# PCB_Actualizada_AMR.net
KiCad netlist of a schematic drawn in EasyEDA
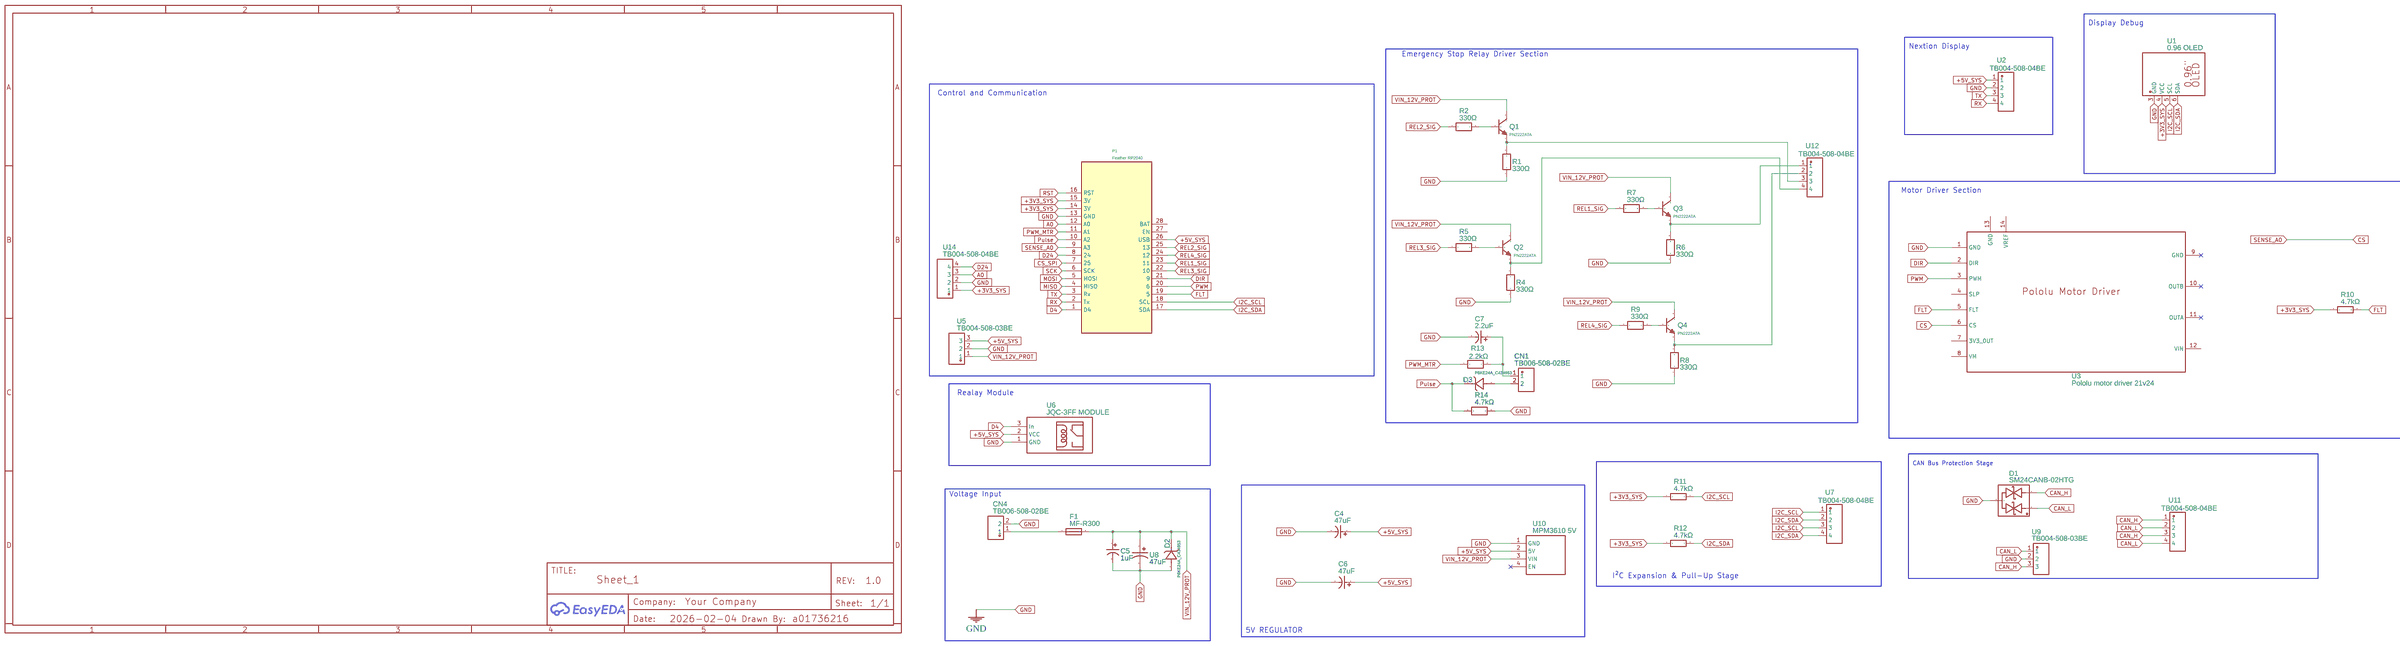
[diagram p0: schematic sheet]

(export (version "E")
  (design (tool "Eeschema 10.0.6"))
  (components
    (comp (ref "C4")
      (value "47uF")
      (fields
        (field (name "Manufacturer Part") "KM476M016D11RR0VH2FP0")
        (field (name "Manufacturer") "Chengx(承兴)")
      )
      (libsource (lib "") (part "47uF 16V Aluminum electrolytic capacitors"))
    )
    (comp (ref "C5")
      (value "1uF")
      (fields
        (field (name "Manufacturer Part") "KM105M250E11RR0VH2FP0")
        (field (name "Manufacturer") "Chengx(承兴)")
      )
      (libsource (lib "") (part "1uF 250V 6.3*11"))
    )
    (comp (ref "C6")
      (value "47uF")
      (fields
        (field (name "Manufacturer Part") "KM476M016D11RR0VH2FP0")
        (field (name "Manufacturer") "Chengx(承兴)")
      )
      (libsource (lib "") (part "47uF 16V Aluminum electrolytic capacitors"))
    )
    (comp (ref "C7")
      (value "2.2uF")
      (fields
        (field (name "Manufacturer Part") "KM476M016D11RR0VH2FP0")
        (field (name "Manufacturer") "Chengx(承兴)")
      )
      (libsource (lib "") (part "47uF 16V Aluminum electrolytic capacitors"))
    )
    (comp (ref "CN1") (value "TB006-508-02BE") (libsource (lib "") (part "TB006-508-02BE")))
    (comp (ref "CN4") (value "TB006-508-02BE") (libsource (lib "") (part "TB006-508-02BE_1")))
    (comp (ref "D1")
      (value "SM24CANB-02HTG")
      (fields (field (name "Manufacturer") "Littelfuse(美国力特)"))
      (libsource (lib "") (part "SM24CANB-02HTG"))
    )
    (comp (ref "D2")
      (value "P6KE24A_C434953")
      (fields (field (name "Manufacturer Part") "P6KE24A") (field (name "Manufacturer") "CREATEK(达晶微)"))
      (libsource (lib "") (part "P6KE24A_C434953"))
    )
    (comp (ref "D3")
      (value "P6KE24A_C434953")
      (fields (field (name "Manufacturer Part") "P6KE24A") (field (name "Manufacturer") "CREATEK(达晶微)"))
      (libsource (lib "") (part "P6KE24A_C434953_1"))
    )
    (comp (ref "F1")
      (value "MF-R300")
      (fields (field (name "Manufacturer") "BOURNS"))
      (libsource (lib "") (part "MF-R300"))
    )
    (comp (ref "P1")
      (value "Feather RP2040")
      (fields (field (name "Manufacturer") "Adafruit"))
      (libsource (lib "") (part "Feather RP2040"))
    )
    (comp (ref "Q1")
      (value "PN2222ATA")
      (fields (field (name "Manufacturer") "onsemi(安森美)"))
      (libsource (lib "") (part "PN2222ATA"))
    )
    (comp (ref "Q2")
      (value "PN2222ATA")
      (fields (field (name "Manufacturer") "onsemi(安森美)"))
      (libsource (lib "") (part "PN2222ATA"))
    )
    (comp (ref "Q3")
      (value "PN2222ATA")
      (fields (field (name "Manufacturer") "onsemi(安森美)"))
      (libsource (lib "") (part "PN2222ATA"))
    )
    (comp (ref "Q4")
      (value "PN2222ATA")
      (fields (field (name "Manufacturer") "onsemi(安森美)"))
      (libsource (lib "") (part "PN2222ATA"))
    )
    (comp (ref "R1")
      (value "330Ω")
      (fields
        (field (name "Manufacturer Part") "RN 1/4W 330R F T/B A1")
        (field (name "Manufacturer") "Tyohm(幸亚电阻)")
      )
      (libsource (lib "") (part "RN 1/4W 330R F T/B A1"))
    )
    (comp (ref "R2")
      (value "330Ω")
      (fields
        (field (name "Manufacturer Part") "RN 1/4W 330R F T/B A1")
        (field (name "Manufacturer") "Tyohm(幸亚电阻)")
      )
      (libsource (lib "") (part "RN 1/4W 330R F T/B A1_1"))
    )
    (comp (ref "R4")
      (value "330Ω")
      (fields
        (field (name "Manufacturer Part") "RN 1/4W 330R F T/B A1")
        (field (name "Manufacturer") "Tyohm(幸亚电阻)")
      )
      (libsource (lib "") (part "RN 1/4W 330R F T/B A1"))
    )
    (comp (ref "R5")
      (value "330Ω")
      (fields
        (field (name "Manufacturer Part") "RN 1/4W 330R F T/B A1")
        (field (name "Manufacturer") "Tyohm(幸亚电阻)")
      )
      (libsource (lib "") (part "RN 1/4W 330R F T/B A1_1"))
    )
    (comp (ref "R6")
      (value "330Ω")
      (fields
        (field (name "Manufacturer Part") "RN 1/4W 330R F T/B A1")
        (field (name "Manufacturer") "Tyohm(幸亚电阻)")
      )
      (libsource (lib "") (part "RN 1/4W 330R F T/B A1"))
    )
    (comp (ref "R7")
      (value "330Ω")
      (fields
        (field (name "Manufacturer Part") "RN 1/4W 330R F T/B A1")
        (field (name "Manufacturer") "Tyohm(幸亚电阻)")
      )
      (libsource (lib "") (part "RN 1/4W 330R F T/B A1_1"))
    )
    (comp (ref "R8")
      (value "330Ω")
      (fields
        (field (name "Manufacturer Part") "RN 1/4W 330R F T/B A1")
        (field (name "Manufacturer") "Tyohm(幸亚电阻)")
      )
      (libsource (lib "") (part "RN 1/4W 330R F T/B A1"))
    )
    (comp (ref "R9")
      (value "330Ω")
      (fields
        (field (name "Manufacturer Part") "RN 1/4W 330R F T/B A1")
        (field (name "Manufacturer") "Tyohm(幸亚电阻)")
      )
      (libsource (lib "") (part "RN 1/4W 330R F T/B A1_1"))
    )
    (comp (ref "R10")
      (value "4.7kΩ")
      (fields
        (field (name "Manufacturer Part") "CF1/4W-4.7KΩ±5% T")
        (field (name "Manufacturer") "CCO(千志电子)")
      )
      (libsource (lib "") (part "CF1/4W-4.7KΩ±5% T52"))
    )
    (comp (ref "R11")
      (value "4.7kΩ")
      (fields
        (field (name "Manufacturer Part") "CF1/4W-4.7KΩ±5% T")
        (field (name "Manufacturer") "CCO(千志电子)")
      )
      (libsource (lib "") (part "CF1/4W-4.7KΩ±5% T52"))
    )
    (comp (ref "R12")
      (value "4.7kΩ")
      (fields
        (field (name "Manufacturer Part") "CF1/4W-4.7KΩ±5% T")
        (field (name "Manufacturer") "CCO(千志电子)")
      )
      (libsource (lib "") (part "CF1/4W-4.7KΩ±5% T52"))
    )
    (comp (ref "R13")
      (value "2.2kΩ")
      (fields
        (field (name "Manufacturer Part") "RN 1/4W 330R F T/B A1")
        (field (name "Manufacturer") "Tyohm(幸亚电阻)")
      )
      (libsource (lib "") (part "RN 1/4W 330R F T/B A1_1"))
    )
    (comp (ref "R14")
      (value "4.7kΩ")
      (fields
        (field (name "Manufacturer Part") "RN 1/4W 330R F T/B A1")
        (field (name "Manufacturer") "Tyohm(幸亚电阻)")
      )
      (libsource (lib "") (part "RN 1/4W 330R F T/B A1_1"))
    )
    (comp (ref "U1")
      (value "0.96 OLED")
      (fields
        (field (name "Manufacturer Part") "ZJY096S0700BG01蓝色")
        (field (name "Manufacturer") "AZDelivery")
      )
      (libsource (lib "") (part "0.96 OLED"))
    )
    (comp (ref "U2")
      (value "TB004-508-04BE")
      (fields (field (name "Manufacturer") "CUI"))
      (libsource (lib "") (part "TB004-508-04BE"))
    )
    (comp (ref "U3")
      (value "Pololu motor driver 21v24")
      (libsource (lib "") (part "Pololu motor driver 18v25"))
    )
    (comp (ref "U5")
      (value "TB004-508-03BE")
      (fields (field (name "Manufacturer") "CUI"))
      (libsource (lib "") (part "TB004-508-03BE_1"))
    )
    (comp (ref "U6")
      (value "JQC-3FF MODULE")
      (fields (field (name "Manufacturer Part") "JQC-3FF"))
      (libsource (lib "") (part "JQC-3FF MODULE"))
    )
    (comp (ref "U7")
      (value "TB004-508-04BE")
      (fields (field (name "Manufacturer") "CUI"))
      (libsource (lib "") (part "TB004-508-04BE"))
    )
    (comp (ref "U8")
      (value "47uF")
      (fields (field (name "Manufacturer Part") "25V47uF CD110") (field (name "Manufacturer") "HRK(鸿瑞凯电子)"))
      (libsource (lib "") (part "25V47UF CD110"))
    )
    (comp (ref "U9")
      (value "TB004-508-03BE")
      (fields (field (name "Manufacturer") "CUI"))
      (libsource (lib "") (part "TB004-508-03BE"))
    )
    (comp (ref "U10")
      (value "MPM3610 5V")
      (fields (field (name "Manufacturer Part") "4739") (field (name "Manufacturer") "Adafruit"))
      (libsource (lib "") (part "MPM3610 5V"))
    )
    (comp (ref "U11")
      (value "TB004-508-04BE")
      (fields (field (name "Manufacturer") "CUI"))
      (libsource (lib "") (part "TB004-508-04BE"))
    )
    (comp (ref "U12")
      (value "TB004-508-04BE")
      (fields (field (name "Manufacturer") "CUI"))
      (libsource (lib "") (part "TB004-508-04BE"))
    )
    (comp (ref "U14")
      (value "TB004-508-04BE")
      (fields (field (name "Manufacturer") "CUI"))
      (libsource (lib "") (part "TB004-508-04BE_1"))
    )
  )
  (nets
    (net (code "1") (name "+3V3_SYS") (class "Default")
      (node (ref "P1") (pin "14") (pinfunction "3V_14") (pintype "unspecified"))
      (node (ref "P1") (pin "15") (pinfunction "3V_15") (pintype "unspecified"))
      (node (ref "R10") (pin "1") (pinfunction "1_1") (pintype "unspecified"))
      (node (ref "R11") (pin "1") (pinfunction "1_1") (pintype "unspecified"))
      (node (ref "R12") (pin "1") (pinfunction "1_1") (pintype "unspecified"))
      (node (ref "U1") (pin "4") (pinfunction "VCC_4") (pintype "unspecified"))
      (node (ref "U14") (pin "1") (pinfunction "1_1") (pintype "unspecified"))
    )
    (net (code "2") (name "+5V_SYS") (class "Default")
      (node (ref "C4") (pin "1") (pinfunction "1_1") (pintype "input"))
      (node (ref "C6") (pin "1") (pinfunction "1_1") (pintype "input"))
      (node (ref "P1") (pin "26") (pinfunction "USB_26") (pintype "unspecified"))
      (node (ref "U10") (pin "2") (pinfunction "5V_2") (pintype "unspecified"))
      (node (ref "U2") (pin "1") (pinfunction "1_1") (pintype "unspecified"))
      (node (ref "U5") (pin "3") (pinfunction "3_3") (pintype "unspecified"))
      (node (ref "U6") (pin "2") (pinfunction "VCC_2") (pintype "unspecified"))
    )
    (net (code "3") (name "A0") (class "Default")
      (node (ref "P1") (pin "12") (pinfunction "A0_12") (pintype "unspecified"))
      (node (ref "U14") (pin "3") (pinfunction "3_3") (pintype "unspecified"))
    )
    (net (code "4") (name "CAN_H") (class "Default")
      (node (ref "D1") (pin "2") (pinfunction "2_2") (pintype "unspecified"))
      (node (ref "U11") (pin "1") (pinfunction "1_1") (pintype "unspecified"))
      (node (ref "U11") (pin "3") (pinfunction "3_3") (pintype "unspecified"))
      (node (ref "U9") (pin "3") (pinfunction "3_3") (pintype "unspecified"))
    )
    (net (code "5") (name "CAN_L") (class "Default")
      (node (ref "D1") (pin "1") (pinfunction "1_1") (pintype "unspecified"))
      (node (ref "U11") (pin "2") (pinfunction "2_2") (pintype "unspecified"))
      (node (ref "U11") (pin "4") (pinfunction "4_4") (pintype "unspecified"))
      (node (ref "U9") (pin "1") (pinfunction "1_1") (pintype "unspecified"))
    )
    (net (code "6") (name "CS") (class "Default")
      (node (ref "P1") (pin "9") (pinfunction "A3_9") (pintype "unspecified"))
      (node (ref "U3") (pin "6") (pinfunction "CS_6") (pintype "unspecified"))
    )
    (net (code "7") (name "CS_SPI") (class "Default")
      (node (ref "P1") (pin "7") (pinfunction "25_7") (pintype "unspecified"))
    )
    (net (code "8") (name "D4") (class "Default")
      (node (ref "P1") (pin "1") (pinfunction "D4_1") (pintype "unspecified"))
      (node (ref "U6") (pin "3") (pinfunction "In_3") (pintype "unspecified"))
    )
    (net (code "9") (name "D24") (class "Default")
      (node (ref "P1") (pin "8") (pinfunction "24_8") (pintype "unspecified"))
      (node (ref "U14") (pin "4") (pinfunction "4_4") (pintype "unspecified"))
    )
    (net (code "10") (name "DIR") (class "Default")
      (node (ref "P1") (pin "21") (pinfunction "9_21") (pintype "unspecified"))
      (node (ref "U3") (pin "2") (pinfunction "DIR_2") (pintype "unspecified"))
    )
    (net (code "11") (name "FLT") (class "Default")
      (node (ref "P1") (pin "19") (pinfunction "5_19") (pintype "unspecified"))
      (node (ref "R10") (pin "2") (pinfunction "2_2") (pintype "unspecified"))
      (node (ref "U3") (pin "5") (pinfunction "FLT_5") (pintype "unspecified"))
    )
    (net (code "12") (name "GND") (class "Default")
      (node (ref "C4") (pin "2") (pinfunction "2_2") (pintype "input"))
      (node (ref "C5") (pin "2") (pinfunction "2_2") (pintype "input"))
      (node (ref "C6") (pin "2") (pinfunction "2_2") (pintype "input"))
      (node (ref "C7") (pin "2") (pinfunction "2_2") (pintype "input"))
      (node (ref "CN4") (pin "2") (pinfunction "2_2") (pintype "unspecified"))
      (node (ref "D1") (pin "3") (pinfunction "3_3") (pintype "unspecified"))
      (node (ref "D2") (pin "2") (pinfunction "A_2") (pintype "unspecified"))
      (node (ref "P1") (pin "13") (pinfunction "GND_13") (pintype "unspecified"))
      (node (ref "R1") (pin "1") (pinfunction "1_1") (pintype "unspecified"))
      (node (ref "R14") (pin "2") (pinfunction "2_2") (pintype "unspecified"))
      (node (ref "R4") (pin "1") (pinfunction "1_1") (pintype "unspecified"))
      (node (ref "R6") (pin "1") (pinfunction "1_1") (pintype "unspecified"))
      (node (ref "R8") (pin "1") (pinfunction "1_1") (pintype "unspecified"))
      (node (ref "U1") (pin "3") (pinfunction "GND_3") (pintype "unspecified"))
      (node (ref "U10") (pin "1") (pinfunction "GND_1") (pintype "unspecified"))
      (node (ref "U14") (pin "2") (pinfunction "2_2") (pintype "unspecified"))
      (node (ref "U2") (pin "2") (pinfunction "2_2") (pintype "unspecified"))
      (node (ref "U3") (pin "1") (pinfunction "GND_1") (pintype "unspecified"))
      (node (ref "U5") (pin "2") (pinfunction "2_2") (pintype "unspecified"))
      (node (ref "U6") (pin "1") (pinfunction "GND_1") (pintype "unspecified"))
      (node (ref "U8") (pin "2") (pinfunction "2_2") (pintype "unspecified"))
      (node (ref "U9") (pin "2") (pinfunction "2_2") (pintype "unspecified"))
    )
    (net (code "13") (name "I2C_SCL") (class "Default")
      (node (ref "P1") (pin "18") (pinfunction "SCL_18") (pintype "unspecified"))
      (node (ref "R11") (pin "2") (pinfunction "2_2") (pintype "unspecified"))
      (node (ref "U1") (pin "5") (pinfunction "SCL_5") (pintype "unspecified"))
      (node (ref "U7") (pin "1") (pinfunction "1_1") (pintype "unspecified"))
      (node (ref "U7") (pin "3") (pinfunction "3_3") (pintype "unspecified"))
    )
    (net (code "14") (name "I2C_SDA") (class "Default")
      (node (ref "P1") (pin "17") (pinfunction "SDA_17") (pintype "unspecified"))
      (node (ref "R12") (pin "2") (pinfunction "2_2") (pintype "unspecified"))
      (node (ref "U1") (pin "6") (pinfunction "SDA_6") (pintype "unspecified"))
      (node (ref "U7") (pin "2") (pinfunction "2_2") (pintype "unspecified"))
      (node (ref "U7") (pin "4") (pinfunction "4_4") (pintype "unspecified"))
    )
    (net (code "15") (name "MISO") (class "Default")
      (node (ref "P1") (pin "4") (pinfunction "MISO_4") (pintype "unspecified"))
    )
    (net (code "16") (name "MOSI") (class "Default")
      (node (ref "P1") (pin "5") (pinfunction "MOSI_5") (pintype "unspecified"))
    )
    (net (code "17") (name "Net-(C7-Pad1)") (class "Default")
      (node (ref "C7") (pin "1") (pinfunction "1_1") (pintype "input"))
      (node (ref "CN1") (pin "1") (pinfunction "1_1") (pintype "unspecified"))
      (node (ref "R13") (pin "2") (pinfunction "2_2") (pintype "unspecified"))
    )
    (net (code "18") (name "Net-(CN4-Pad1)") (class "Default")
      (node (ref "CN4") (pin "1") (pinfunction "1_1") (pintype "unspecified"))
      (node (ref "F1") (pin "1") (pinfunction "1_1") (pintype "unspecified"))
    )
    (net (code "19") (name "Net-(D3-A)") (class "Default")
      (node (ref "CN1") (pin "2") (pinfunction "2_2") (pintype "unspecified"))
      (node (ref "D3") (pin "2") (pinfunction "A_2") (pintype "unspecified"))
    )
    (net (code "20") (name "Net-(Q1-B)") (class "Default")
      (node (ref "Q1") (pin "2") (pinfunction "B_2") (pintype "unspecified"))
      (node (ref "R2") (pin "2") (pinfunction "2_2") (pintype "unspecified"))
    )
    (net (code "21") (name "Net-(Q1-E)") (class "Default")
      (node (ref "Q1") (pin "1") (pinfunction "E_1") (pintype "unspecified"))
      (node (ref "R1") (pin "2") (pinfunction "2_2") (pintype "unspecified"))
      (node (ref "U12") (pin "3") (pinfunction "3_3") (pintype "unspecified"))
    )
    (net (code "22") (name "Net-(Q2-B)") (class "Default")
      (node (ref "Q2") (pin "2") (pinfunction "B_2") (pintype "unspecified"))
      (node (ref "R5") (pin "2") (pinfunction "2_2") (pintype "unspecified"))
    )
    (net (code "23") (name "Net-(Q2-E)") (class "Default")
      (node (ref "Q2") (pin "1") (pinfunction "E_1") (pintype "unspecified"))
      (node (ref "R4") (pin "2") (pinfunction "2_2") (pintype "unspecified"))
      (node (ref "U12") (pin "4") (pinfunction "4_4") (pintype "unspecified"))
    )
    (net (code "24") (name "Net-(Q3-B)") (class "Default")
      (node (ref "Q3") (pin "2") (pinfunction "B_2") (pintype "unspecified"))
      (node (ref "R7") (pin "2") (pinfunction "2_2") (pintype "unspecified"))
    )
    (net (code "25") (name "Net-(Q3-E)") (class "Default")
      (node (ref "Q3") (pin "1") (pinfunction "E_1") (pintype "unspecified"))
      (node (ref "R6") (pin "2") (pinfunction "2_2") (pintype "unspecified"))
      (node (ref "U12") (pin "1") (pinfunction "1_1") (pintype "unspecified"))
    )
    (net (code "26") (name "Net-(Q4-B)") (class "Default")
      (node (ref "Q4") (pin "2") (pinfunction "B_2") (pintype "unspecified"))
      (node (ref "R9") (pin "2") (pinfunction "2_2") (pintype "unspecified"))
    )
    (net (code "27") (name "Net-(Q4-E)") (class "Default")
      (node (ref "Q4") (pin "1") (pinfunction "E_1") (pintype "unspecified"))
      (node (ref "R8") (pin "2") (pinfunction "2_2") (pintype "unspecified"))
      (node (ref "U12") (pin "2") (pinfunction "2_2") (pintype "unspecified"))
    )
    (net (code "28") (name "PWM") (class "Default")
      (node (ref "P1") (pin "20") (pinfunction "6_20") (pintype "unspecified"))
      (node (ref "U3") (pin "3") (pinfunction "PWM_3") (pintype "unspecified"))
    )
    (net (code "29") (name "PWM_MTR") (class "Default")
      (node (ref "P1") (pin "11") (pinfunction "A1_11") (pintype "unspecified"))
      (node (ref "R13") (pin "1") (pinfunction "1_1") (pintype "unspecified"))
    )
    (net (code "30") (name "Pulse") (class "Default")
      (node (ref "D3") (pin "1") (pinfunction "C_1") (pintype "unspecified"))
      (node (ref "P1") (pin "10") (pinfunction "A2_10") (pintype "unspecified"))
      (node (ref "R14") (pin "1") (pinfunction "1_1") (pintype "unspecified"))
    )
    (net (code "31") (name "REL1_SIG") (class "Default")
      (node (ref "P1") (pin "23") (pinfunction "11_23") (pintype "unspecified"))
      (node (ref "R7") (pin "1") (pinfunction "1_1") (pintype "unspecified"))
    )
    (net (code "32") (name "REL2_SIG") (class "Default")
      (node (ref "P1") (pin "25") (pinfunction "13_25") (pintype "unspecified"))
      (node (ref "R2") (pin "1") (pinfunction "1_1") (pintype "unspecified"))
    )
    (net (code "33") (name "REL3_SIG") (class "Default")
      (node (ref "P1") (pin "22") (pinfunction "10_22") (pintype "unspecified"))
      (node (ref "R5") (pin "1") (pinfunction "1_1") (pintype "unspecified"))
    )
    (net (code "34") (name "REL4_SIG") (class "Default")
      (node (ref "P1") (pin "24") (pinfunction "12_24") (pintype "unspecified"))
      (node (ref "R9") (pin "1") (pinfunction "1_1") (pintype "unspecified"))
    )
    (net (code "35") (name "RST") (class "Default")
      (node (ref "P1") (pin "16") (pinfunction "RST_16") (pintype "unspecified"))
    )
    (net (code "36") (name "RX") (class "Default")
      (node (ref "P1") (pin "2") (pinfunction "Tx_2") (pintype "unspecified"))
      (node (ref "U2") (pin "4") (pinfunction "4_4") (pintype "unspecified"))
    )
    (net (code "37") (name "SCK") (class "Default")
      (node (ref "P1") (pin "6") (pinfunction "SCK_6") (pintype "unspecified"))
    )
    (net (code "38") (name "TX") (class "Default")
      (node (ref "P1") (pin "3") (pinfunction "Rx_3") (pintype "unspecified"))
      (node (ref "U2") (pin "3") (pinfunction "3_3") (pintype "unspecified"))
    )
    (net (code "39") (name "VIN_12V_PROT") (class "Default")
      (node (ref "C5") (pin "1") (pinfunction "1_1") (pintype "input"))
      (node (ref "D2") (pin "1") (pinfunction "C_1") (pintype "unspecified"))
      (node (ref "F1") (pin "2") (pinfunction "2_2") (pintype "unspecified"))
      (node (ref "Q1") (pin "3") (pinfunction "C_3") (pintype "unspecified"))
      (node (ref "Q2") (pin "3") (pinfunction "C_3") (pintype "unspecified"))
      (node (ref "Q3") (pin "3") (pinfunction "C_3") (pintype "unspecified"))
      (node (ref "Q4") (pin "3") (pinfunction "C_3") (pintype "unspecified"))
      (node (ref "U10") (pin "3") (pinfunction "VIN_3") (pintype "unspecified"))
      (node (ref "U5") (pin "1") (pinfunction "1_1") (pintype "unspecified"))
      (node (ref "U8") (pin "1") (pinfunction "1_1") (pintype "unspecified"))
    )
    (net (code "40") (name "unconnected-(P1-BAT-Pad28)") (class "Default")
      (node (ref "P1") (pin "28") (pinfunction "BAT_28") (pintype "unspecified"))
    )
    (net (code "41") (name "unconnected-(P1-EN-Pad27)") (class "Default")
      (node (ref "P1") (pin "27") (pinfunction "EN_27") (pintype "unspecified"))
    )
    (net (code "42") (name "unconnected-(U3-3V3_0UT-Pad7)") (class "Default")
      (node (ref "U3") (pin "7") (pinfunction "3V3_0UT_7") (pintype "unspecified"))
    )
    (net (code "43") (name "unconnected-(U3-GND-Pad9)") (class "Default")
      (node (ref "U3") (pin "9") (pinfunction "GND_9") (pintype "unspecified+no_connect"))
    )
    (net (code "44") (name "unconnected-(U3-GND-Pad13)") (class "Default")
      (node (ref "U3") (pin "13") (pinfunction "GND_13") (pintype "unspecified"))
    )
    (net (code "45") (name "unconnected-(U3-OUTA-Pad11)") (class "Default")
      (node (ref "U3") (pin "11") (pinfunction "OUTA_11") (pintype "unspecified+no_connect"))
    )
    (net (code "46") (name "unconnected-(U3-OUTB-Pad10)") (class "Default")
      (node (ref "U3") (pin "10") (pinfunction "OUTB_10") (pintype "unspecified+no_connect"))
    )
    (net (code "47") (name "unconnected-(U3-SLP-Pad4)") (class "Default")
      (node (ref "U3") (pin "4") (pinfunction "SLP_4") (pintype "unspecified"))
    )
    (net (code "48") (name "unconnected-(U3-VIN-Pad12)") (class "Default")
      (node (ref "U3") (pin "12") (pinfunction "VIN_12") (pintype "unspecified"))
    )
    (net (code "49") (name "unconnected-(U3-VM-Pad8)") (class "Default")
      (node (ref "U3") (pin "8") (pinfunction "VM_8") (pintype "unspecified"))
    )
    (net (code "50") (name "unconnected-(U3-VREF-Pad14)") (class "Default")
      (node (ref "U3") (pin "14") (pinfunction "VREF_14") (pintype "unspecified"))
    )
    (net (code "51") (name "unconnected-(U10-EN-Pad4)") (class "Default")
      (node (ref "U10") (pin "4") (pinfunction "EN_4") (pintype "unspecified+no_connect"))
    )
  )
)
